# RS422_RX.net
KiCad netlist of a schematic drawn in Altium Designer
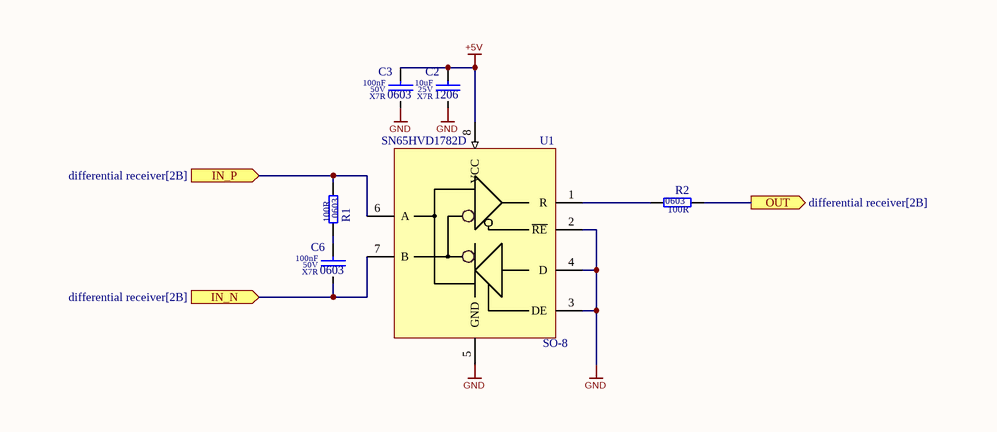
[diagram p0: RS422_RX.SchDoc]

(export (version "E")
  (design (tool "Eeschema 10.0.6"))
  (components
    (comp (ref "C2")
      (value "10uF")
      (footprint "C_1206_3216")
      (description "Capacitor")
      (fields
        (field (name "DIELECTRIC") "X7R")
        (field (name "VOLTAGE") "25V")
        (field (name "SCH_FOOTPRINT") "1206")
        (field (name "PART NUMBER") "C_10uF_25V_X7R_1206_10")
        (field (name "MANUFACTURER") "Samsung")
      )
      (libsource (lib "Library") (part "C"))
    )
    (comp (ref "C3")
      (value "100nF")
      (footprint "C_0603_1608")
      (description "Capacitor")
      (fields
        (field (name "DIELECTRIC") "X7R")
        (field (name "VOLTAGE") "50V")
        (field (name "SCH_FOOTPRINT") "0603")
        (field (name "PART NUMBER") "C_100nF_50V_X7R_0603_5")
        (field (name "MANUFACTURER") "Samsung")
      )
      (libsource (lib "Library") (part "C"))
    )
    (comp (ref "C6")
      (value "100nF")
      (footprint "C_0603_1608")
      (description "Capacitor")
      (fields
        (field (name "DIELECTRIC") "X7R")
        (field (name "VOLTAGE") "50V")
        (field (name "SCH_FOOTPRINT") "0603")
        (field (name "PART NUMBER") "C_100nF_50V_X7R_0603_5")
        (field (name "MANUFACTURER") "Samsung")
      )
      (libsource (lib "Library") (part "C"))
    )
    (comp (ref "R1")
      (value "100R")
      (footprint "R_0603_1608")
      (fields
        (field (name "SCH_FOOTPRINT") "0603")
        (field (name "PART NUMBER") "R_100R_0603_1_AECQ0")
        (field (name "VOLTAGE") "75V")
        (field (name "POWER") "100mW")
      )
      (libsource (lib "Library") (part "R"))
    )
    (comp (ref "R2")
      (value "100R")
      (footprint "R_0603_1608")
      (fields
        (field (name "SCH_FOOTPRINT") "0603")
        (field (name "PART NUMBER") "R_100R_0603_1")
        (field (name "VOLTAGE") "50V")
        (field (name "POWER") "100mW")
      )
      (libsource (lib "Library") (part "R"))
    )
    (comp (ref "U1")
      (value "SN65HVD1782D")
      (footprint "SOP8_SO8_SOIC8_4X5X18")
      (description "Fault-Protected  RS-485  Transceivers  With 3.3-V to 5-V Operation")
      (fields
        (field (name "SCH_FOOTPRINT") "SO-8")
        (field (name "PART NUMBER") "U_SN65HVD1782DR")
        (field (name "MANUFACTURER") "Texas Instruments")
      )
      (libsource (lib "Library") (part "U_RS485_HD_GENERIC"))
    )
  )
  (nets
    (net (code "1") (name "+5V") (class "Default")
      (node (ref "C2") (pin "1") (pinfunction "1_1") (pintype "passive"))
      (node (ref "C3") (pin "1") (pinfunction "1_1") (pintype "passive"))
      (node (ref "U1") (pin "8") (pinfunction "VCC_8") (pintype "input"))
    )
    (net (code "2") (name "/IN_N") (class "Default")
      (node (ref "C6") (pin "2") (pinfunction "2_2") (pintype "passive"))
      (node (ref "U1") (pin "7") (pinfunction "B_7") (pintype "passive"))
    )
    (net (code "3") (name "/IN_P") (class "Default")
      (node (ref "R1") (pin "2") (pinfunction "2_2") (pintype "passive"))
      (node (ref "U1") (pin "6") (pinfunction "A_6") (pintype "passive"))
    )
    (net (code "4") (name "/OUT") (class "Default")
      (node (ref "R2") (pin "1") (pinfunction "1_1") (pintype "passive"))
    )
    (net (code "5") (name "GND") (class "Default")
      (node (ref "C2") (pin "2") (pinfunction "2_2") (pintype "passive"))
      (node (ref "C3") (pin "2") (pinfunction "2_2") (pintype "passive"))
      (node (ref "U1") (pin "2") (pinfunction "~{RE}_2") (pintype "passive"))
      (node (ref "U1") (pin "3") (pinfunction "DE_3") (pintype "passive"))
      (node (ref "U1") (pin "4") (pinfunction "D_4") (pintype "passive"))
      (node (ref "U1") (pin "5") (pinfunction "GND_5") (pintype "power_in"))
    )
    (net (code "6") (name "Net-(C6-Pad1)") (class "Default")
      (node (ref "C6") (pin "1") (pinfunction "1_1") (pintype "passive"))
      (node (ref "R1") (pin "1") (pinfunction "1_1") (pintype "passive"))
    )
    (net (code "7") (name "Net-(U1-R)") (class "Default")
      (node (ref "R2") (pin "2") (pinfunction "2_2") (pintype "passive"))
      (node (ref "U1") (pin "1") (pinfunction "R_1") (pintype "passive"))
    )
  )
)
